# AdelinoX3.net
KiCad netlist of a schematic drawn in EAGLE
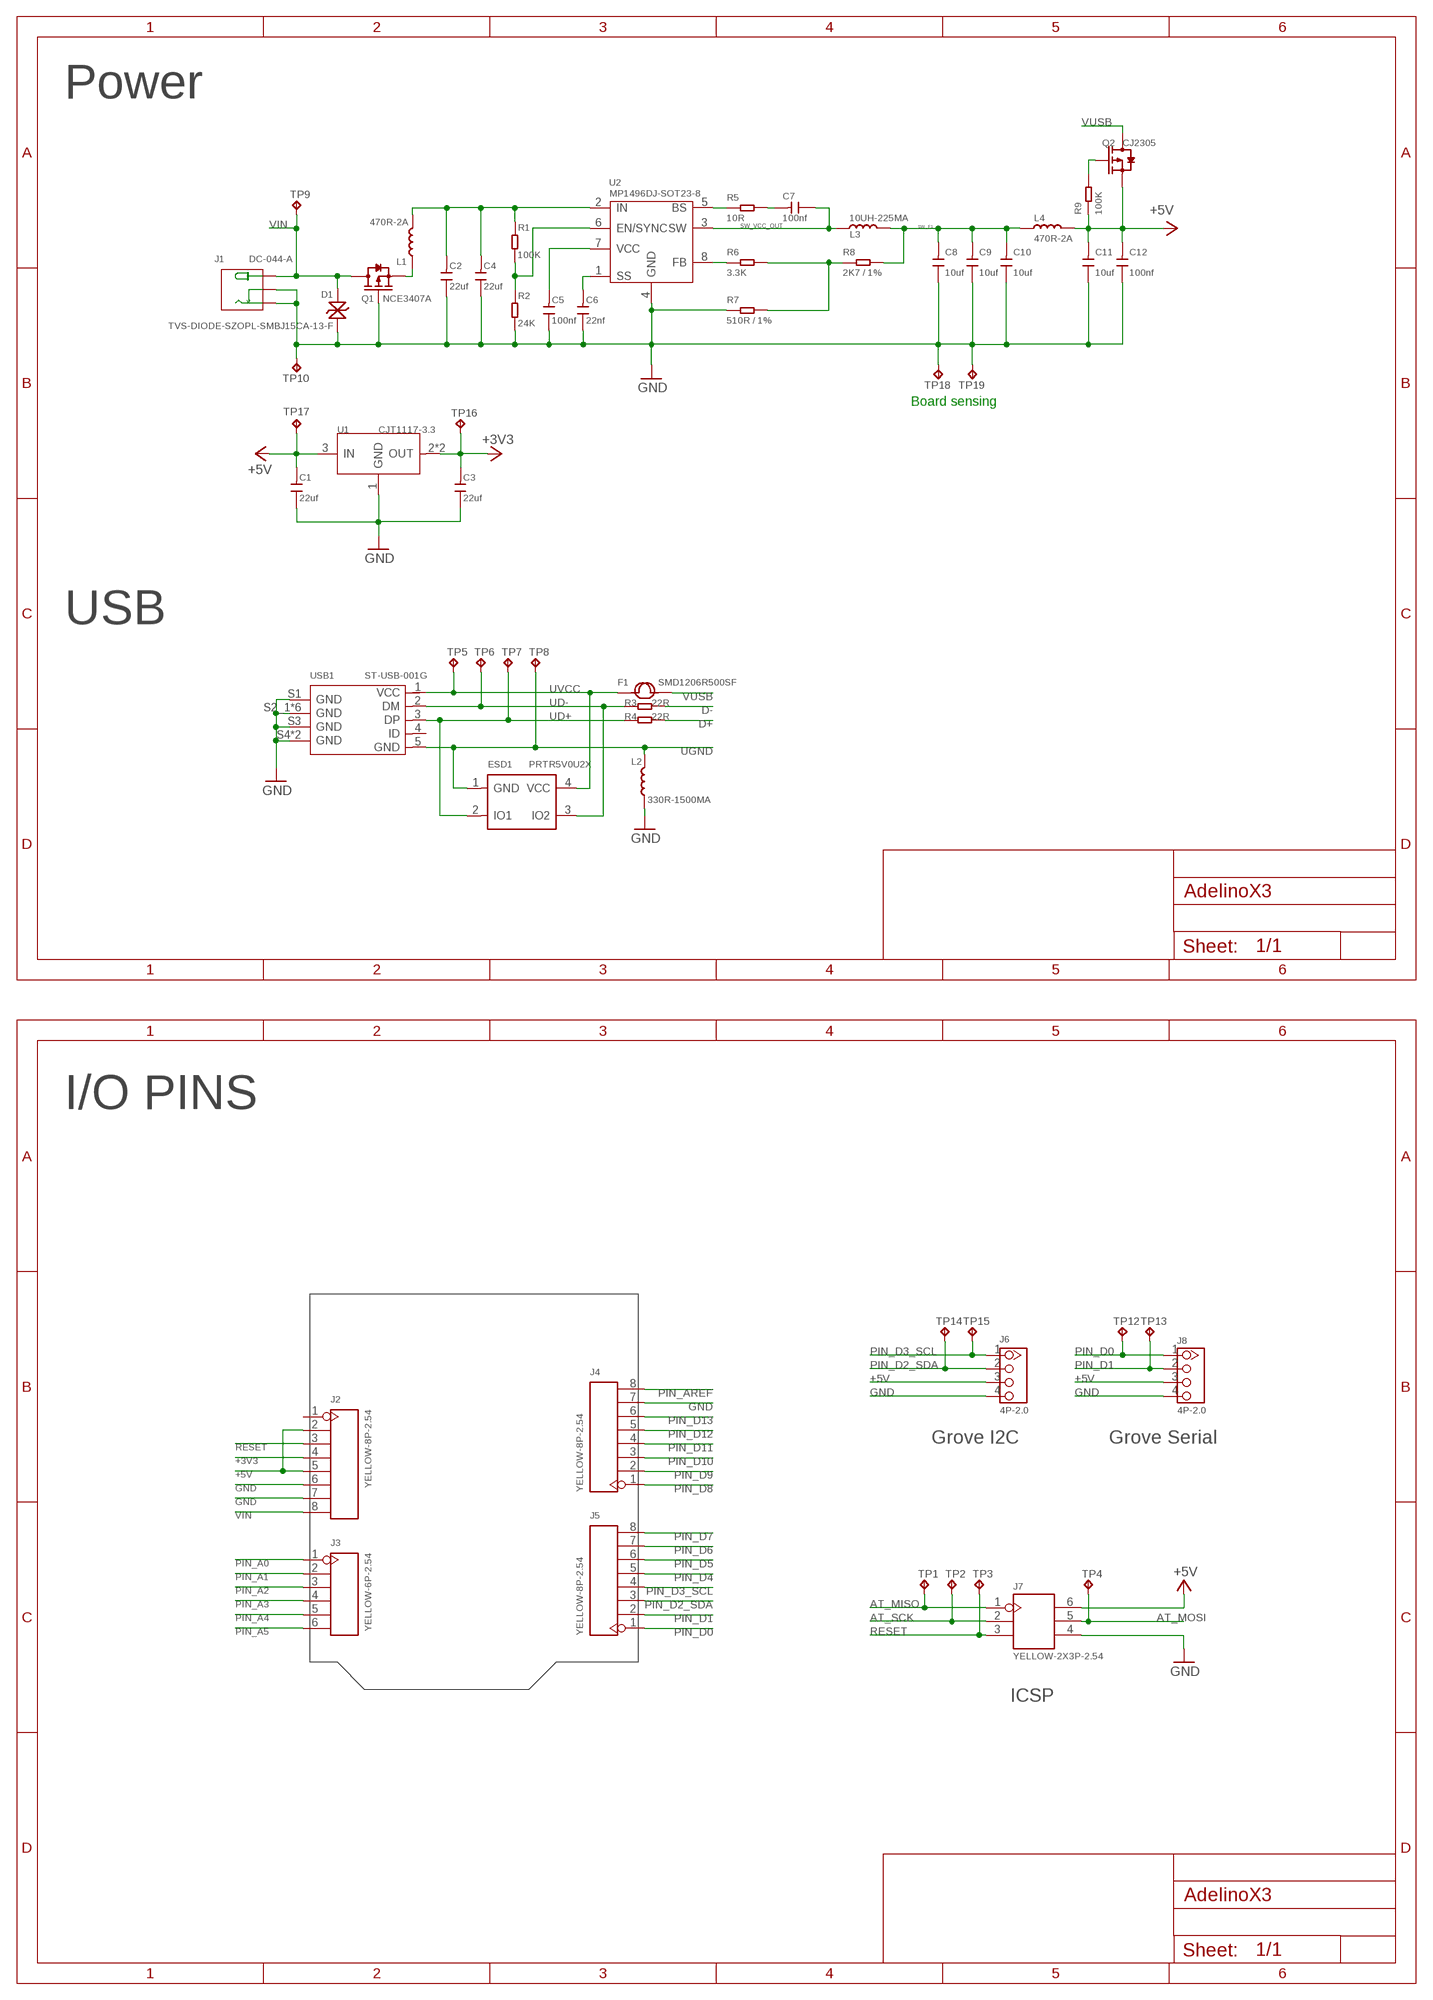
[diagram p0: schematic, sheet 1, part 1 of 2]
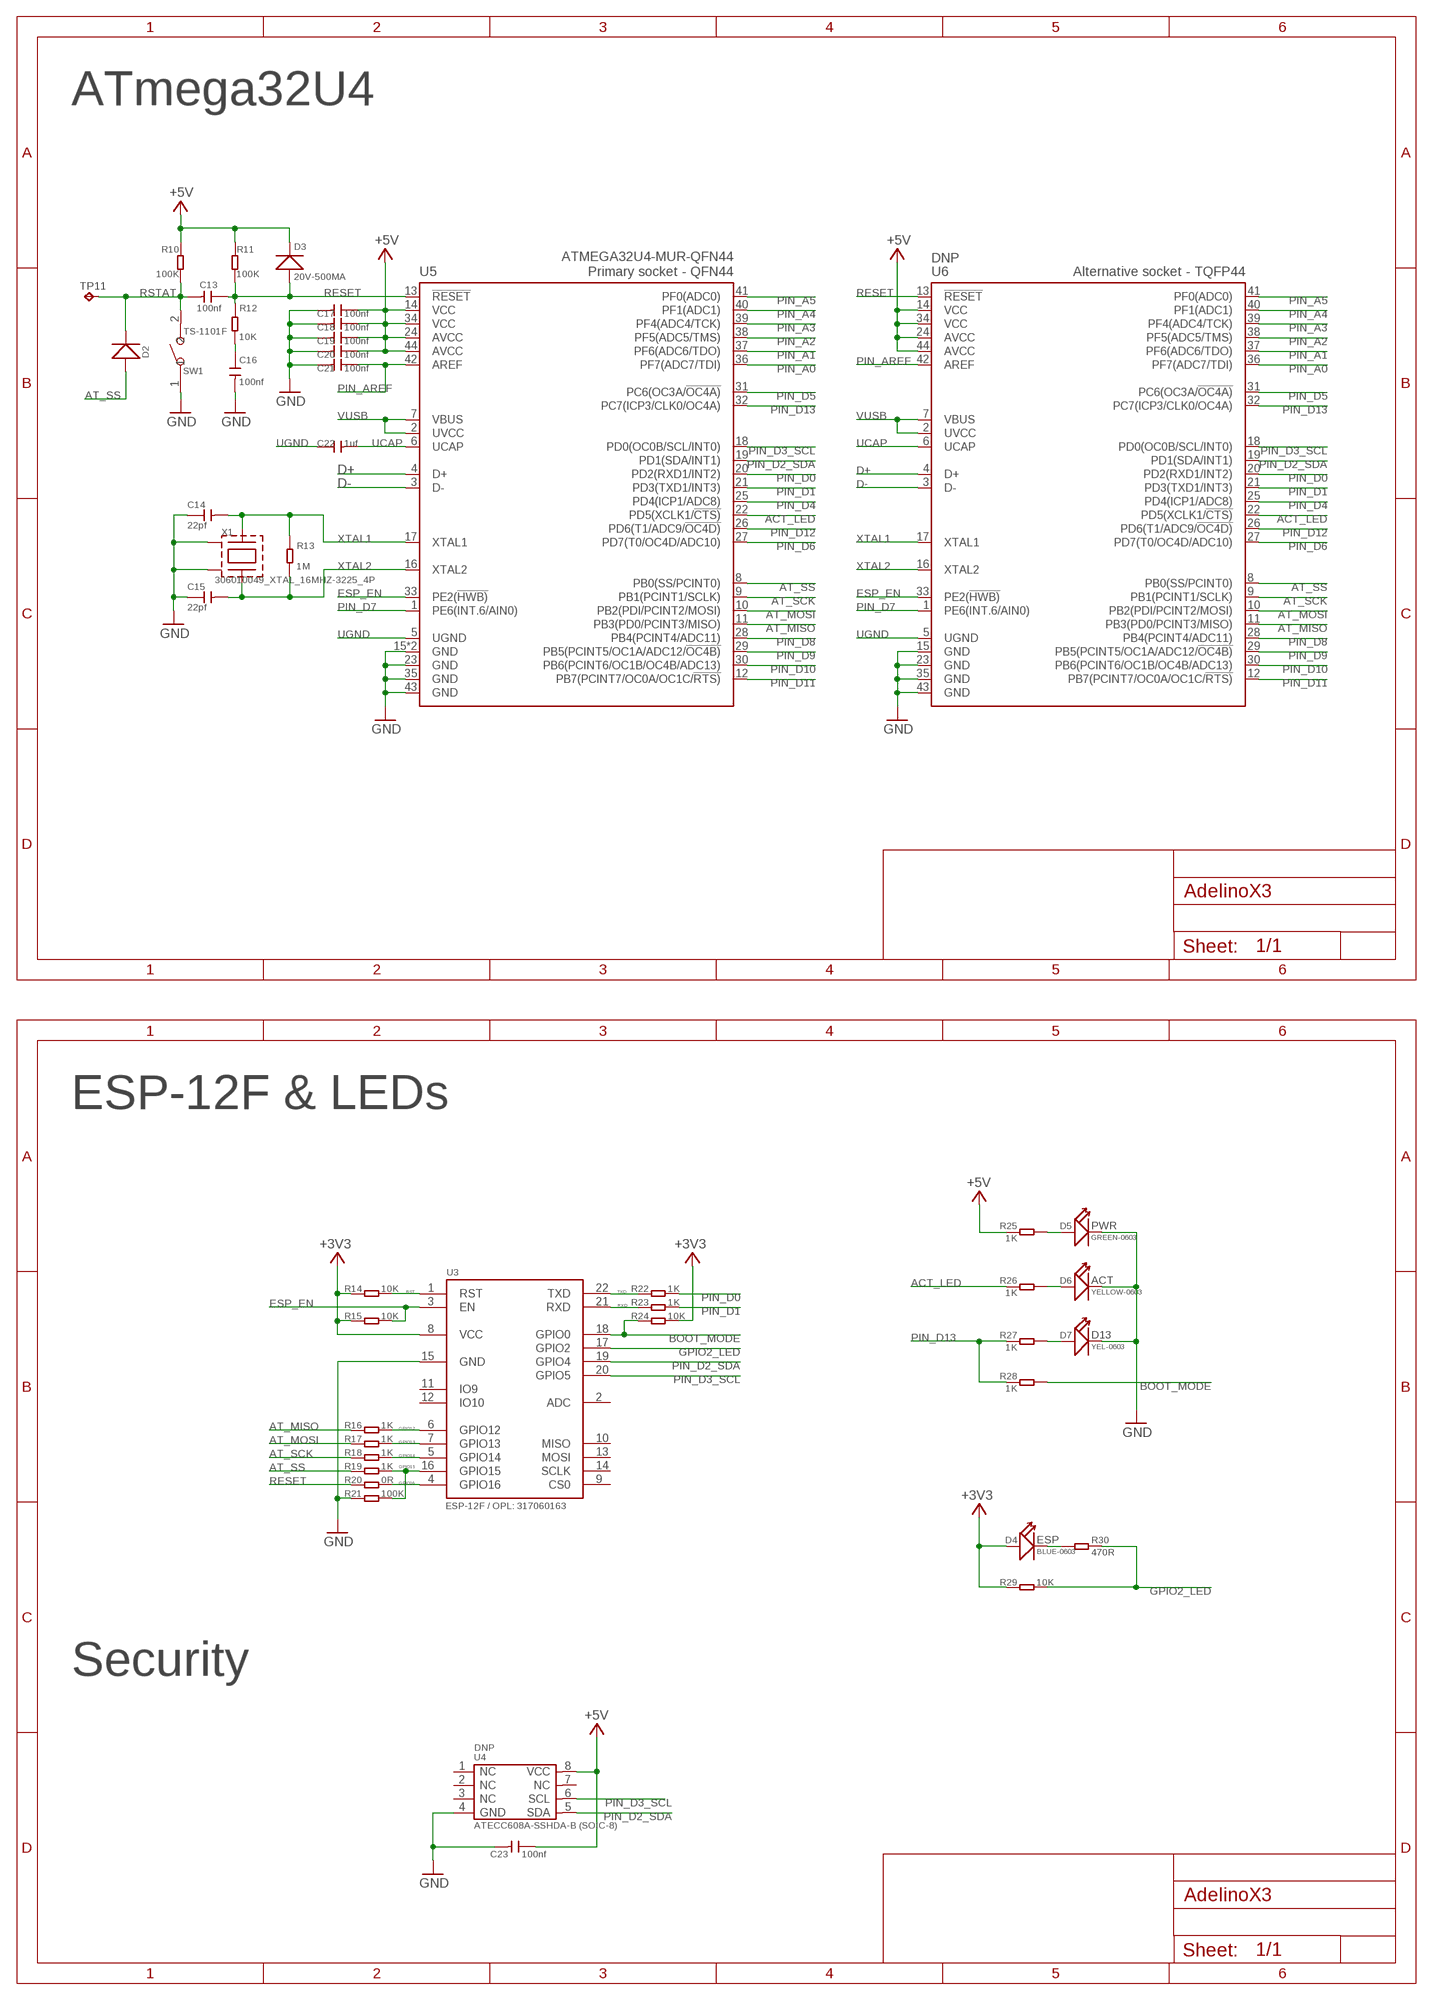
[diagram p1: schematic, sheet 1, part 2 of 2]

(export (version "E")
  (design (tool "Eeschema 10.0.6"))
  (components
    (comp (ref "C1")
      (value "22uf")
      (footprint "eagle-import:C1206")
      (libsource (lib "eagle-import") (part "Seeed-Capacitor_CERAMIC-22UF-16V-10%-X7R(1206)"))
    )
    (comp (ref "C2")
      (value "22uf")
      (footprint "eagle-import:C1206")
      (libsource (lib "eagle-import") (part "Seeed-Capacitor_CERAMIC-22UF-16V-10%-X7R(1206)"))
    )
    (comp (ref "C3")
      (value "22uf")
      (footprint "eagle-import:C1206")
      (libsource (lib "eagle-import") (part "CERAMIC-22UF-16V-10%-X7R(1206)"))
    )
    (comp (ref "C4")
      (value "22uf")
      (footprint "eagle-import:C1206")
      (libsource (lib "eagle-import") (part "Seeed-Capacitor_CERAMIC-22UF-16V-10%-X7R(1206)"))
    )
    (comp (ref "C5")
      (value "100nf")
      (footprint "eagle-import:C0603")
      (fields (field (name "MPN") "CC0603KRX7R9BB104"))
      (libsource (lib "eagle-import") (part "CERAMIC-100NF-50V-10%-X7R(0603)"))
    )
    (comp (ref "C6")
      (value "22nf")
      (footprint "eagle-import:C0603")
      (fields (field (name "MPN") "CC0603KRX7R9BB223"))
      (libsource (lib "eagle-import") (part "CERAMIC-22NF-50V-10%-X7R(0603)"))
    )
    (comp (ref "C7")
      (value "100nf")
      (footprint "eagle-import:C0603")
      (fields (field (name "MPN") "CC0603KRX7R9BB104"))
      (libsource (lib "eagle-import") (part "CERAMIC-100NF-50V-10%-X7R(0603)"))
    )
    (comp (ref "C8")
      (value "10uf")
      (footprint "eagle-import:C0805")
      (fields (field (name "MPN") "CC0805KKX5R8BB106"))
      (libsource (lib "eagle-import") (part "CERAMIC-10UF-25V-10%-X5R(0805)"))
    )
    (comp (ref "C9")
      (value "10uf")
      (footprint "eagle-import:C0805")
      (fields (field (name "MPN") "CC0805KKX5R8BB106"))
      (libsource (lib "eagle-import") (part "CERAMIC-10UF-25V-10%-X5R(0805)"))
    )
    (comp (ref "C10")
      (value "10uf")
      (footprint "eagle-import:C0805")
      (fields (field (name "MPN") "CC0805KKX5R8BB106"))
      (libsource (lib "eagle-import") (part "CERAMIC-10UF-25V-10%-X5R(0805)"))
    )
    (comp (ref "C11")
      (value "10uf")
      (footprint "eagle-import:C0805")
      (fields (field (name "MPN") "CC0805KKX5R8BB106"))
      (libsource (lib "eagle-import") (part "CERAMIC-10UF-25V-10%-X5R(0805)"))
    )
    (comp (ref "C12")
      (value "100nf")
      (footprint "eagle-import:C0603")
      (fields (field (name "MPN") "CC0603KRX7R9BB104"))
      (libsource (lib "eagle-import") (part "CERAMIC-100NF-50V-10%-X7R(0603)"))
    )
    (comp (ref "C13")
      (value "100nf")
      (footprint "eagle-import:C0603")
      (fields (field (name "MPN") "CC0603KRX7R9BB104"))
      (libsource (lib "eagle-import") (part "CERAMIC-100NF-50V-10%-X7R(0603)"))
    )
    (comp (ref "C14")
      (value "22pf")
      (footprint "eagle-import:C0603")
      (fields (field (name "MPN") "CC0603JRNPO9BN220"))
      (libsource (lib "eagle-import") (part "CERAMIC-22PF-50V-5%-NPO(0603)"))
    )
    (comp (ref "C15")
      (value "22pf")
      (footprint "eagle-import:C0603")
      (fields (field (name "MPN") "CC0603JRNPO9BN220"))
      (libsource (lib "eagle-import") (part "CERAMIC-22PF-50V-5%-NPO(0603)"))
    )
    (comp (ref "C16")
      (value "100nf")
      (footprint "eagle-import:C0603")
      (fields (field (name "MPN") "CC0603KRX7R9BB104"))
      (libsource (lib "eagle-import") (part "CERAMIC-100NF-50V-10%-X7R(0603)"))
    )
    (comp (ref "C17")
      (value "100nf")
      (footprint "eagle-import:C0603")
      (fields (field (name "MPN") "CC0603KRX7R9BB104"))
      (libsource (lib "eagle-import") (part "CERAMIC-100NF-50V-10%-X7R(0603)"))
    )
    (comp (ref "C18")
      (value "100nf")
      (footprint "eagle-import:C0603")
      (fields (field (name "MPN") "CC0603KRX7R9BB104"))
      (libsource (lib "eagle-import") (part "CERAMIC-100NF-50V-10%-X7R(0603)"))
    )
    (comp (ref "C19")
      (value "100nf")
      (footprint "eagle-import:C0603")
      (fields (field (name "MPN") "CC0603KRX7R9BB104"))
      (libsource (lib "eagle-import") (part "CERAMIC-100NF-50V-10%-X7R(0603)"))
    )
    (comp (ref "C20")
      (value "100nf")
      (footprint "eagle-import:C0603")
      (fields (field (name "MPN") "CC0603KRX7R9BB104"))
      (libsource (lib "eagle-import") (part "CERAMIC-100NF-50V-10%-X7R(0603)"))
    )
    (comp (ref "C21")
      (value "100nf")
      (footprint "eagle-import:C0603")
      (fields (field (name "MPN") "CC0603KRX7R9BB104"))
      (libsource (lib "eagle-import") (part "CERAMIC-100NF-50V-10%-X7R(0603)"))
    )
    (comp (ref "C22")
      (value "1uf")
      (footprint "eagle-import:C0603")
      (fields (field (name "MPN") "CC0603KRX7R8BB105"))
      (libsource (lib "eagle-import") (part "CERAMIC-1UF-25V-10%-X7R(0603)"))
    )
    (comp (ref "C23")
      (value "100nf")
      (footprint "eagle-import:C0603")
      (fields (field (name "MPN") "CC0603KRX7R9BB104"))
      (libsource (lib "eagle-import") (part "Seeed-Capacitor_CERAMIC-100NF-50V-10%-X7R(0603)"))
    )
    (comp (ref "D1")
      (value "TVS-DIODE-SZOPL-SMBJ15CA-13-F")
      (footprint "eagle-import:DO-214AA")
      (fields (field (name "MPN") "SMBJ15CA-13-F"))
      (libsource (lib "eagle-import") (part "TVS-DIODE-SZOPL-SMBJ15CA-13-F"))
    )
    (comp (ref "D2")
      (value "20V-500MA")
      (footprint "eagle-import:SOD-123")
      (fields (field (name "MPN") "MBR0520LT1G"))
      (libsource (lib "eagle-import") (part "SMD-DIODE-SCHOTTKY-20V-500MA(SOD-123)P"))
    )
    (comp (ref "D3")
      (value "20V-500MA")
      (footprint "eagle-import:SOD-123")
      (fields (field (name "MPN") "MBR0520LT1G"))
      (libsource (lib "eagle-import") (part "SMD-DIODE-SCHOTTKY-20V-500MA(SOD-123)P"))
    )
    (comp (ref "D4")
      (value "BLUE-0603")
      (footprint "eagle-import:LED-0603")
      (fields (field (name "MPN") "19-217-BHC-ZL1M2RY-3T") (field (name "LABEL") "ESP"))
      (libsource (lib "eagle-import") (part "SMD-LED-CLEAR-BLUE(0603)"))
    )
    (comp (ref "D5")
      (value "GREEN-0603")
      (footprint "eagle-import:LED-0603")
      (fields (field (name "MPN") "19-217-G7C-AN1P2-3T") (field (name "LABEL") "PWR"))
      (libsource (lib "eagle-import") (part "SMD-LED-CLEAR-GREEN(0603)"))
    )
    (comp (ref "D6")
      (value "YELLOW-0603")
      (footprint "eagle-import:LED-0603")
      (fields (field (name "MPN") "19-217-Y5C-AM1N1VY-3T") (field (name "LABEL") "ACT"))
      (libsource (lib "eagle-import") (part "SMD-LED-CLEAR-YELLOW(0603)"))
    )
    (comp (ref "D7")
      (value "YEL-0603")
      (footprint "eagle-import:LED-0603")
      (fields (field (name "MPN") "19-217-Y5C-AM1N1VY-3T") (field (name "LABEL") "D13"))
      (libsource (lib "eagle-import") (part "SMD-LED-CLEAR-YELLOW(0603)"))
    )
    (comp (ref "ESD1")
      (value "PRTR5V0U2X")
      (footprint "eagle-import:SOT-143B")
      (fields (field (name "MPN") "NXP;PRTR5V0U2X,215"))
      (libsource (lib "eagle-import") (part "SMD-DIODE-TVS-5.5V"))
    )
    (comp (ref "F1")
      (value "SMD1206R500SF")
      (footprint "eagle-import:F1206")
      (libsource (lib "eagle-import") (part "SMD-PPTC-500MA(1206)"))
    )
    (comp (ref "J1")
      (value "DC-044-A")
      (footprint "eagle-import:DCJ3P-11.6X9.6X7.0MM")
      (fields (field (name "MPN") "JACK-DC-044-A"))
      (libsource (lib "eagle-import") (part "JACK-DC-044-A"))
    )
    (comp (ref "J2")
      (value "YELLOW-8P-2.54")
      (footprint "eagle-import:H8-2.54")
      (fields (field (name "MPN") "F185-1108A1BSYC1"))
      (libsource (lib "eagle-import") (part "DIP-YELLOW-FEMALE-HEADER(8P-2.54)"))
    )
    (comp (ref "J3")
      (value "YELLOW-6P-2.54")
      (footprint "eagle-import:H6-2.54")
      (fields (field (name "MPN") "F185-1106A1BSYA3"))
      (libsource (lib "eagle-import") (part "DIP-YELLOW-FEMALE-HEADER-VERT(6P-2.54)"))
    )
    (comp (ref "J4")
      (value "YELLOW-8P-2.54")
      (footprint "eagle-import:H8-2.54")
      (fields (field (name "MPN") "F185-1108A1BSYC1"))
      (libsource (lib "eagle-import") (part "DIP-YELLOW-FEMALE-HEADER(8P-2.54)"))
    )
    (comp (ref "J5")
      (value "YELLOW-8P-2.54")
      (footprint "eagle-import:H8-2.54")
      (fields (field (name "MPN") "F185-1108A1BSYC1"))
      (libsource (lib "eagle-import") (part "DIP-YELLOW-FEMALE-HEADER(8P-2.54)"))
    )
    (comp (ref "J6")
      (value "4P-2.0")
      (footprint "eagle-import:HW4-2.0")
      (libsource (lib "eagle-import") (part "GROVE-CONNECTOR-DIP(4P-2.0)"))
    )
    (comp (ref "J7")
      (value "YELLOW-2X3P-2.54")
      (footprint "eagle-import:H2X3-2.54")
      (fields (field (name "MPN") "P125-1203A0BS116A2"))
      (libsource (lib "eagle-import") (part "DIP-YELLOW-MALE-HEADER-VERT(2X3P-2.54)"))
    )
    (comp (ref "J8")
      (value "4P-2.0")
      (footprint "eagle-import:HW4-2.0")
      (libsource (lib "eagle-import") (part "GROVE-CONNECTOR-DIP(4P-2.0)"))
    )
    (comp (ref "L1")
      (value "470R-2A")
      (footprint "eagle-import:L0805")
      (fields (field (name "MPN") "WLB2012-471T20"))
      (libsource (lib "eagle-import") (part "SMD-FERRITE-BEAD-470R-2A(0805)'0805'"))
    )
    (comp (ref "L2")
      (value "330R-1500MA")
      (footprint "eagle-import:L0805")
      (fields (field (name "MPN") "BLM21PG331SN1D"))
      (libsource (lib "eagle-import") (part "SMD-FERRITE-BEAD-330R-1500MA(0805)'0805'"))
    )
    (comp (ref "L3")
      (value "10UH-225MA")
      (footprint "eagle-import:L5040S")
      (libsource (lib "eagle-import") (part "SMD-INDUCTOR-10UH-20%-2.35A(2P-5X5X4MM)"))
    )
    (comp (ref "L4")
      (value "470R-2A")
      (footprint "eagle-import:L0805")
      (fields (field (name "MPN") "WLB2012-471T20"))
      (libsource (lib "eagle-import") (part "SMD-FERRITE-BEAD-470R-2A(0805)'0805'"))
    )
    (comp (ref "Q1")
      (value "NCE3407A")
      (footprint "eagle-import:SOT-23")
      (libsource (lib "eagle-import") (part "SMD-MOSFET-P-CH-VDC=30V-ID=4.3A-NCE3407A(SOT-23)"))
    )
    (comp (ref "Q2")
      (value "CJ2305")
      (footprint "eagle-import:SOT-23")
      (libsource (lib "eagle-import") (part "SMD-MOSFET-P-CH-8V-4.1A-CJ2305(SOT-23)"))
    )
    (comp (ref "R1")
      (value "100K")
      (footprint "eagle-import:R0603")
      (fields (field (name "MPN") "RC0603JR-07100KL"))
      (libsource (lib "eagle-import") (part "SMD-RES-100K-5%-1/10W(0603)"))
    )
    (comp (ref "R2")
      (value "24K")
      (footprint "eagle-import:R0603")
      (libsource (lib "eagle-import") (part "SMD-RES-24K-1%-1/10W(0603)"))
    )
    (comp (ref "R3")
      (value "22R")
      (footprint "eagle-import:R0603")
      (fields (field (name "MPN") "RC0603JR-0722RL"))
      (libsource (lib "eagle-import") (part "SMD-RES-22R-5%-1/10W(0603)"))
    )
    (comp (ref "R4")
      (value "22R")
      (footprint "eagle-import:R0603")
      (fields (field (name "MPN") "RC0603JR-0722RL"))
      (libsource (lib "eagle-import") (part "SMD-RES-22R-5%-1/10W(0603)"))
    )
    (comp (ref "R5")
      (value "10R")
      (footprint "eagle-import:R0603")
      (fields (field (name "MPN") "RC0603FR-0710RL"))
      (libsource (lib "eagle-import") (part "SMD-RES-10R-1%-1/10W(0603)"))
    )
    (comp (ref "R6")
      (value "3.3K")
      (footprint "eagle-import:R0603")
      (libsource (lib "eagle-import") (part "SMD-RES-3.3K-5%-1/10W(0603)"))
    )
    (comp (ref "R7")
      (value "3K / 1%")
      (footprint "eagle-import:R0603")
      (fields (field (name "R") "510R / 1%"))
      (libsource (lib "eagle-import") (part "SMD-RES-510R-1%-1/10W(0603)"))
    )
    (comp (ref "R8")
      (value "2K7 / 1%")
      (footprint "eagle-import:R0603")
      (fields (field (name "R") "2K7 / 1%"))
      (libsource (lib "eagle-import") (part "SMD-RES-2.7K-1%-1/10W(0603)"))
    )
    (comp (ref "R9")
      (value "100K")
      (footprint "eagle-import:R0603")
      (fields (field (name "MPN") "RC0603JR-07100KL"))
      (libsource (lib "eagle-import") (part "SMD-RES-100K-5%-1/10W(0603)"))
    )
    (comp (ref "R10")
      (value "100K")
      (footprint "eagle-import:R0603")
      (fields (field (name "MPN") "RC0603JR-07100KL"))
      (libsource (lib "eagle-import") (part "SMD-RES-100K-5%-1/10W(0603)"))
    )
    (comp (ref "R11")
      (value "100K")
      (footprint "eagle-import:R0603")
      (fields (field (name "MPN") "RC0603JR-07100KL"))
      (libsource (lib "eagle-import") (part "SMD-RES-100K-5%-1/10W(0603)"))
    )
    (comp (ref "R12")
      (value "10K")
      (footprint "eagle-import:R0603")
      (fields (field (name "MPN") "RC0603JR-0710KL"))
      (libsource (lib "eagle-import") (part "SMD-RES-10K-5%-1/10W(0603)"))
    )
    (comp (ref "R13")
      (value "1M")
      (footprint "eagle-import:R0603")
      (fields (field (name "MPN") "RC0603JR-071ML"))
      (libsource (lib "eagle-import") (part "SMD-RES-1M-5%-1/10W(0603)"))
    )
    (comp (ref "R14")
      (value "10K")
      (footprint "eagle-import:R0603")
      (fields (field (name "MPN") "RC0603JR-0710KL"))
      (libsource (lib "eagle-import") (part "SMD-RES-10K-5%-1/10W(0603)"))
    )
    (comp (ref "R15")
      (value "10K")
      (footprint "eagle-import:R0603")
      (fields (field (name "MPN") "RC0603JR-0710KL"))
      (libsource (lib "eagle-import") (part "SMD-RES-10K-5%-1/10W(0603)"))
    )
    (comp (ref "R16")
      (value "1K")
      (footprint "eagle-import:R0603")
      (fields (field (name "MPN") "RC0603JR-071KL"))
      (libsource (lib "eagle-import") (part "SMD-RES-1K-5%-1/10W(0603)"))
    )
    (comp (ref "R17")
      (value "1K")
      (footprint "eagle-import:R0603")
      (fields (field (name "MPN") "RC0603JR-071KL"))
      (libsource (lib "eagle-import") (part "SMD-RES-1K-5%-1/10W(0603)"))
    )
    (comp (ref "R18")
      (value "1K")
      (footprint "eagle-import:R0603")
      (fields (field (name "MPN") "RC0603JR-071KL"))
      (libsource (lib "eagle-import") (part "SMD-RES-1K-5%-1/10W(0603)"))
    )
    (comp (ref "R19")
      (value "1K")
      (footprint "eagle-import:R0603")
      (fields (field (name "MPN") "RC0603JR-071KL"))
      (libsource (lib "eagle-import") (part "SMD-RES-1K-5%-1/10W(0603)"))
    )
    (comp (ref "R20")
      (value "0R")
      (footprint "eagle-import:R0603")
      (fields (field (name "MPN") "RC0603JR-070RL"))
      (libsource (lib "eagle-import") (part "SMD-RES-0R-5%-1/10W(0603)"))
    )
    (comp (ref "R21")
      (value "100K")
      (footprint "eagle-import:R0603")
      (fields (field (name "MPN") "RC0603JR-07100KL"))
      (libsource (lib "eagle-import") (part "SMD-RES-100K-5%-1/10W(0603)"))
    )
    (comp (ref "R22")
      (value "1K")
      (footprint "eagle-import:R0603")
      (fields (field (name "MPN") "RC0603JR-071KL"))
      (libsource (lib "eagle-import") (part "SMD-RES-1K-5%-1/10W(0603)"))
    )
    (comp (ref "R23")
      (value "1K")
      (footprint "eagle-import:R0603")
      (fields (field (name "MPN") "RC0603JR-071KL"))
      (libsource (lib "eagle-import") (part "SMD-RES-1K-5%-1/10W(0603)"))
    )
    (comp (ref "R24")
      (value "10K")
      (footprint "eagle-import:R0603")
      (fields (field (name "MPN") "RC0603JR-0710KL"))
      (libsource (lib "eagle-import") (part "SMD-RES-10K-5%-1/10W(0603)"))
    )
    (comp (ref "R25")
      (value "1K")
      (footprint "eagle-import:R0603")
      (fields (field (name "MPN") "RC0603JR-071KL"))
      (libsource (lib "eagle-import") (part "SMD-RES-1K-5%-1/10W(0603)"))
    )
    (comp (ref "R26")
      (value "1K")
      (footprint "eagle-import:R0603")
      (fields (field (name "MPN") "RC0603JR-071KL"))
      (libsource (lib "eagle-import") (part "SMD-RES-1K-5%-1/10W(0603)"))
    )
    (comp (ref "R27")
      (value "1K")
      (footprint "eagle-import:R0603")
      (fields (field (name "MPN") "RC0603JR-071KL"))
      (libsource (lib "eagle-import") (part "SMD-RES-1K-5%-1/10W(0603)"))
    )
    (comp (ref "R28")
      (value "1K")
      (footprint "eagle-import:R0603")
      (fields (field (name "MPN") "RC0603JR-071KL"))
      (libsource (lib "eagle-import") (part "SMD-RES-1K-5%-1/10W(0603)"))
    )
    (comp (ref "R29")
      (value "10K")
      (footprint "eagle-import:R0603")
      (fields (field (name "MPN") "RC0603JR-0710KL"))
      (libsource (lib "eagle-import") (part "SMD-RES-10K-5%-1/10W(0603)"))
    )
    (comp (ref "R30")
      (value "470R")
      (footprint "eagle-import:R0603")
      (fields (field (name "MPN") "RC0603JR-07470RL"))
      (libsource (lib "eagle-import") (part "SMD-RES-470R-5%-1/10W(0603)"))
    )
    (comp (ref "SW1")
      (value "TS-1101F")
      (footprint "eagle-import:SW2-5.0-6.0X3.0X4.3MM")
      (libsource (lib "eagle-import") (part "DIP-BUTTON(2P-6.0X3.0X4.3MM)-TS-1101F"))
    )
    (comp (ref "TP1")
      (value "TPTP16R")
      (footprint "eagle-import:TP16R")
      (libsource (lib "eagle-import") (part "TPTP16R"))
    )
    (comp (ref "TP2")
      (value "TPTP16R")
      (footprint "eagle-import:TP16R")
      (libsource (lib "eagle-import") (part "TPTP16R"))
    )
    (comp (ref "TP3")
      (value "TPTP16R")
      (footprint "eagle-import:TP16R")
      (libsource (lib "eagle-import") (part "TPTP16R"))
    )
    (comp (ref "TP4")
      (value "TPTP16R")
      (footprint "eagle-import:TP16R")
      (libsource (lib "eagle-import") (part "TPTP16R"))
    )
    (comp (ref "TP5")
      (value "TPTP16R")
      (footprint "eagle-import:TP16R")
      (libsource (lib "eagle-import") (part "TPTP16R"))
    )
    (comp (ref "TP6")
      (value "TPTP16R")
      (footprint "eagle-import:TP16R")
      (libsource (lib "eagle-import") (part "TPTP16R"))
    )
    (comp (ref "TP7")
      (value "TPTP16R")
      (footprint "eagle-import:TP16R")
      (libsource (lib "eagle-import") (part "TPTP16R"))
    )
    (comp (ref "TP8")
      (value "TPTP16R")
      (footprint "eagle-import:TP16R")
      (libsource (lib "eagle-import") (part "TPTP16R"))
    )
    (comp (ref "TP9")
      (value "TPTP16R")
      (footprint "eagle-import:TP16R")
      (libsource (lib "eagle-import") (part "TPTP16R"))
    )
    (comp (ref "TP10")
      (value "TPTP16R")
      (footprint "eagle-import:TP16R")
      (libsource (lib "eagle-import") (part "TPTP16R"))
    )
    (comp (ref "TP11")
      (value "TPTP16R")
      (footprint "eagle-import:TP16R")
      (libsource (lib "eagle-import") (part "TPTP16R"))
    )
    (comp (ref "TP12")
      (value "TPTP16R")
      (footprint "eagle-import:TP16R")
      (libsource (lib "eagle-import") (part "TPTP16R"))
    )
    (comp (ref "TP13")
      (value "TPTP16R")
      (footprint "eagle-import:TP16R")
      (libsource (lib "eagle-import") (part "TPTP16R"))
    )
    (comp (ref "TP14")
      (value "TPTP16R")
      (footprint "eagle-import:TP16R")
      (libsource (lib "eagle-import") (part "TPTP16R"))
    )
    (comp (ref "TP15")
      (value "TPTP16R")
      (footprint "eagle-import:TP16R")
      (libsource (lib "eagle-import") (part "TPTP16R"))
    )
    (comp (ref "TP16")
      (value "TPTP16R")
      (footprint "eagle-import:TP16R")
      (libsource (lib "eagle-import") (part "TPTP16R"))
    )
    (comp (ref "TP17")
      (value "TPTP16R")
      (footprint "eagle-import:TP16R")
      (libsource (lib "eagle-import") (part "TPTP16R"))
    )
    (comp (ref "TP18")
      (value "TPTP16R")
      (footprint "eagle-import:TP16R")
      (libsource (lib "eagle-import") (part "TPTP16R"))
    )
    (comp (ref "TP19")
      (value "TPTP16R")
      (footprint "eagle-import:TP16R")
      (libsource (lib "eagle-import") (part "TPTP16R"))
    )
    (comp (ref "U1")
      (value "CJT1117-3.3")
      (footprint "eagle-import:SOT-223")
      (libsource (lib "eagle-import") (part "PMIC-CJT1117-3.3(SOT223)"))
    )
    (comp (ref "U2")
      (value "MP1496DJ-SOT23-8")
      (footprint "eagle-import:SOT-23-8")
      (fields (field (name "MPN") "MP1496DJ"))
      (libsource (lib "eagle-import") (part "PMIC-MP1496DJ(SOT23-8)"))
    )
    (comp (ref "U3")
      (value "ESP-12F / OPL: 317060163")
      (footprint "eagle-import:ESP-12F")
      (libsource (lib "eagle-import") (part "ESP-12F"))
    )
    (comp (ref "U4")
      (value "DNP")
      (footprint "eagle-import:SOIC8-1.27-5X4MM")
      (fields
        (field (name "MPN") "ATECC608")
        (field (name "DESC") "ATECC608A-SSHDA-B (SOIC-8)")
        (field (name "MPN_1") "ATECC608A-SSHDA-B")
      )
      (libsource (lib "eagle-import") (part "ATECC608(SOIC8)"))
    )
    (comp (ref "U5")
      (value "ATMEGA32U4-MUR-QFN44")
      (footprint "eagle-import:QFN44G-0.5-7X7MM")
      (fields (field (name "MPN") "ATMEGA32U4-MUR") (field (name "DESC") "Primary socket - QFN44"))
      (libsource (lib "eagle-import") (part "MCU-ATMEGA32U4-MUR(VQFN44)"))
    )
    (comp (ref "U6")
      (value "DNP")
      (footprint "eagle-import:TQFP44-0.8-9.6X9.6MM")
      (fields (field (name "MPN") "ATMEGA32U4") (field (name "DESC") "Alternative socket - TQFP44"))
      (libsource (lib "eagle-import") (part "MCU-ATMEGA32U4-AU(TQFP44)"))
    )
    (comp (ref "USB1")
      (value "ST-USB-001G")
      (footprint "eagle-import:MICRO-USB5+4P-SMD-0.65-B")
      (libsource (lib "eagle-import") (part "MICRO-USB-SMD-B-WITHOUT-POST-W/P(ST-USB-001G)"))
    )
    (comp (ref "X1")
      (value "306010049_XTAL_16MHZ-3225_4P")
      (footprint "eagle-import:X3225_4P")
      (libsource (lib "eagle-import") (part "306010049_XTAL_16MHZ-3225_4P"))
    )
  )
  (nets
    (net (code "1") (name "+3V3") (class "Default")
      (node (ref "C3") (pin "2") (pinfunction "2_2") (pintype "passive"))
      (node (ref "D4") (pin "+") (pinfunction "+_+") (pintype "passive"))
      (node (ref "J2") (pin "4") (pinfunction "4_4") (pintype "bidirectional"))
      (node (ref "R14") (pin "1") (pinfunction "1_1") (pintype "passive"))
      (node (ref "R15") (pin "1") (pinfunction "1_1") (pintype "passive"))
      (node (ref "R24") (pin "2") (pinfunction "2_2") (pintype "passive"))
      (node (ref "R29") (pin "1") (pinfunction "1_1") (pintype "passive"))
      (node (ref "TP16") (pin "TP") (pinfunction "TP_TP") (pintype "input"))
      (node (ref "U1") (pin "2") (pinfunction "OUT_2") (pintype "bidirectional"))
      (node (ref "U1") (pin "TER") (pinfunction "OUT_TER") (pintype "bidirectional"))
      (node (ref "U3") (pin "8") (pinfunction "VCC_8") (pintype "bidirectional"))
    )
    (net (code "2") (name "+5V") (class "Default")
      (node (ref "C1") (pin "2") (pinfunction "2_2") (pintype "passive"))
      (node (ref "C11") (pin "2") (pinfunction "2_2") (pintype "passive"))
      (node (ref "C12") (pin "2") (pinfunction "2_2") (pintype "passive"))
      (node (ref "C17") (pin "1") (pinfunction "1_1") (pintype "passive"))
      (node (ref "C18") (pin "1") (pinfunction "1_1") (pintype "passive"))
      (node (ref "C19") (pin "1") (pinfunction "1_1") (pintype "passive"))
      (node (ref "C20") (pin "1") (pinfunction "1_1") (pintype "passive"))
      (node (ref "C23") (pin "1") (pinfunction "1_1") (pintype "passive"))
      (node (ref "D3") (pin "-") (pinfunction "-_-") (pintype "passive"))
      (node (ref "J2") (pin "2") (pinfunction "2_2") (pintype "bidirectional"))
      (node (ref "J2") (pin "5") (pinfunction "5_5") (pintype "bidirectional"))
      (node (ref "J6") (pin "3") (pinfunction "3_3") (pintype "bidirectional"))
      (node (ref "J7") (pin "6") (pinfunction "6_6") (pintype "bidirectional"))
      (node (ref "J8") (pin "3") (pinfunction "3_3") (pintype "bidirectional"))
      (node (ref "L4") (pin "2") (pinfunction "2_2") (pintype "passive"))
      (node (ref "Q2") (pin "2") (pinfunction "S_2") (pintype "passive"))
      (node (ref "R10") (pin "1") (pinfunction "1_1") (pintype "passive"))
      (node (ref "R11") (pin "2") (pinfunction "2_2") (pintype "passive"))
      (node (ref "R25") (pin "1") (pinfunction "1_1") (pintype "passive"))
      (node (ref "R9") (pin "1") (pinfunction "1_1") (pintype "passive"))
      (node (ref "TP17") (pin "TP") (pinfunction "TP_TP") (pintype "input"))
      (node (ref "U1") (pin "3") (pinfunction "IN_3") (pintype "bidirectional"))
      (node (ref "U4") (pin "8") (pinfunction "VCC_8") (pintype "power_in"))
      (node (ref "U5") (pin "14") (pinfunction "VCC_14") (pintype "bidirectional"))
      (node (ref "U5") (pin "24") (pinfunction "AVCC_24") (pintype "bidirectional"))
      (node (ref "U5") (pin "34") (pinfunction "VCC_34") (pintype "bidirectional"))
      (node (ref "U5") (pin "44") (pinfunction "AVCC_44") (pintype "bidirectional"))
      (node (ref "U6") (pin "14") (pinfunction "VCC_14") (pintype "bidirectional"))
      (node (ref "U6") (pin "24") (pinfunction "AVCC_24") (pintype "bidirectional"))
      (node (ref "U6") (pin "34") (pinfunction "VCC_34") (pintype "bidirectional"))
      (node (ref "U6") (pin "44") (pinfunction "AVCC_44") (pintype "bidirectional"))
    )
    (net (code "3") (name "/ACT_LED") (class "Default")
      (node (ref "R26") (pin "1") (pinfunction "1_1") (pintype "passive"))
      (node (ref "U5") (pin "22") (pinfunction "PD5(XCLK1/~{CTS})_22") (pintype "bidirectional"))
      (node (ref "U6") (pin "22") (pinfunction "PD5(XCLK1/~{CTS})_22") (pintype "bidirectional"))
    )
    (net (code "4") (name "/AT_MISO") (class "Default")
      (node (ref "J7") (pin "1") (pinfunction "1_1") (pintype "bidirectional"))
      (node (ref "R16") (pin "1") (pinfunction "1_1") (pintype "passive"))
      (node (ref "TP1") (pin "TP") (pinfunction "TP_TP") (pintype "input"))
      (node (ref "U5") (pin "11") (pinfunction "PB3(PD0/PCINT3/MISO)_11") (pintype "bidirectional"))
      (node (ref "U6") (pin "11") (pinfunction "PB3(PD0/PCINT3/MISO)_11") (pintype "bidirectional"))
    )
    (net (code "5") (name "/AT_MOSI") (class "Default")
      (node (ref "J7") (pin "5") (pinfunction "5_5") (pintype "bidirectional"))
      (node (ref "R17") (pin "1") (pinfunction "1_1") (pintype "passive"))
      (node (ref "TP4") (pin "TP") (pinfunction "TP_TP") (pintype "input"))
      (node (ref "U5") (pin "10") (pinfunction "PB2(PDI/PCINT2/MOSI)_10") (pintype "bidirectional"))
      (node (ref "U6") (pin "10") (pinfunction "PB2(PDI/PCINT2/MOSI)_10") (pintype "bidirectional"))
    )
    (net (code "6") (name "/AT_SCK") (class "Default")
      (node (ref "J7") (pin "2") (pinfunction "2_2") (pintype "bidirectional"))
      (node (ref "R18") (pin "1") (pinfunction "1_1") (pintype "passive"))
      (node (ref "TP2") (pin "TP") (pinfunction "TP_TP") (pintype "input"))
      (node (ref "U5") (pin "9") (pinfunction "PB1(PCINT1/SCLK)_9") (pintype "bidirectional"))
      (node (ref "U6") (pin "9") (pinfunction "PB1(PCINT1/SCLK)_9") (pintype "bidirectional"))
    )
    (net (code "7") (name "/AT_SS") (class "Default")
      (node (ref "D2") (pin "+") (pinfunction "+_+") (pintype "passive"))
      (node (ref "R19") (pin "1") (pinfunction "1_1") (pintype "passive"))
      (node (ref "U5") (pin "8") (pinfunction "PB0(SS/PCINT0)_8") (pintype "bidirectional"))
      (node (ref "U6") (pin "8") (pinfunction "PB0(SS/PCINT0)_8") (pintype "bidirectional"))
    )
    (net (code "8") (name "/BOOT_MODE") (class "Default")
      (node (ref "R24") (pin "1") (pinfunction "1_1") (pintype "passive"))
      (node (ref "R28") (pin "2") (pinfunction "2_2") (pintype "passive"))
      (node (ref "U3") (pin "18") (pinfunction "GPIO0_18") (pintype "bidirectional"))
    )
    (net (code "9") (name "/D+") (class "Default")
      (node (ref "R4") (pin "2") (pinfunction "2_2") (pintype "passive"))
      (node (ref "U5") (pin "4") (pinfunction "D+_4") (pintype "bidirectional"))
      (node (ref "U6") (pin "4") (pinfunction "D+_4") (pintype "bidirectional"))
    )
    (net (code "10") (name "/D-") (class "Default")
      (node (ref "R3") (pin "2") (pinfunction "2_2") (pintype "passive"))
      (node (ref "U5") (pin "3") (pinfunction "D-_3") (pintype "bidirectional"))
      (node (ref "U6") (pin "3") (pinfunction "D-_3") (pintype "bidirectional"))
    )
    (net (code "11") (name "/ESP_EN") (class "Default")
      (node (ref "R15") (pin "2") (pinfunction "2_2") (pintype "passive"))
      (node (ref "U3") (pin "3") (pinfunction "EN_3") (pintype "bidirectional"))
      (node (ref "U5") (pin "33") (pinfunction "PE2(~{HWB})_33") (pintype "bidirectional"))
      (node (ref "U6") (pin "33") (pinfunction "PE2(~{HWB})_33") (pintype "bidirectional"))
    )
    (net (code "12") (name "/GPIO2_LED") (class "Default")
      (node (ref "R29") (pin "2") (pinfunction "2_2") (pintype "passive"))
      (node (ref "R30") (pin "2") (pinfunction "2_2") (pintype "passive"))
      (node (ref "U3") (pin "17") (pinfunction "GPIO2_17") (pintype "bidirectional"))
    )
    (net (code "13") (name "/GPIO12") (class "Default")
      (node (ref "R16") (pin "2") (pinfunction "2_2") (pintype "passive"))
      (node (ref "U3") (pin "6") (pinfunction "GPIO12_6") (pintype "bidirectional"))
    )
    (net (code "14") (name "/GPIO13") (class "Default")
      (node (ref "R17") (pin "2") (pinfunction "2_2") (pintype "passive"))
      (node (ref "U3") (pin "7") (pinfunction "GPIO13_7") (pintype "bidirectional"))
    )
    (net (code "15") (name "/GPIO14") (class "Default")
      (node (ref "R18") (pin "2") (pinfunction "2_2") (pintype "passive"))
      (node (ref "U3") (pin "5") (pinfunction "GPIO14_5") (pintype "bidirectional"))
    )
    (net (code "16") (name "/GPIO15") (class "Default")
      (node (ref "R19") (pin "2") (pinfunction "2_2") (pintype "passive"))
      (node (ref "R21") (pin "2") (pinfunction "2_2") (pintype "passive"))
      (node (ref "U3") (pin "16") (pinfunction "GPIO15_16") (pintype "bidirectional"))
    )
    (net (code "17") (name "/GPIO16") (class "Default")
      (node (ref "R20") (pin "2") (pinfunction "2_2") (pintype "passive"))
      (node (ref "U3") (pin "4") (pinfunction "GPIO16_4") (pintype "bidirectional"))
    )
    (net (code "18") (name "/PIN_A0") (class "Default")
      (node (ref "J3") (pin "1") (pinfunction "1_1") (pintype "bidirectional"))
      (node (ref "U5") (pin "36") (pinfunction "PF7(ADC7/TDI)_36") (pintype "bidirectional"))
      (node (ref "U6") (pin "36") (pinfunction "PF7(ADC7/TDI)_36") (pintype "bidirectional"))
    )
    (net (code "19") (name "/PIN_A1") (class "Default")
      (node (ref "J3") (pin "2") (pinfunction "2_2") (pintype "bidirectional"))
      (node (ref "U5") (pin "37") (pinfunction "PF6(ADC6/TDO)_37") (pintype "bidirectional"))
      (node (ref "U6") (pin "37") (pinfunction "PF6(ADC6/TDO)_37") (pintype "bidirectional"))
    )
    (net (code "20") (name "/PIN_A2") (class "Default")
      (node (ref "J3") (pin "3") (pinfunction "3_3") (pintype "bidirectional"))
      (node (ref "U5") (pin "38") (pinfunction "PF5(ADC5/TMS)_38") (pintype "bidirectional"))
      (node (ref "U6") (pin "38") (pinfunction "PF5(ADC5/TMS)_38") (pintype "bidirectional"))
    )
    (net (code "21") (name "/PIN_A3") (class "Default")
      (node (ref "J3") (pin "4") (pinfunction "4_4") (pintype "bidirectional"))
      (node (ref "U5") (pin "39") (pinfunction "PF4(ADC4/TCK)_39") (pintype "bidirectional"))
      (node (ref "U6") (pin "39") (pinfunction "PF4(ADC4/TCK)_39") (pintype "bidirectional"))
    )
    (net (code "22") (name "/PIN_A4") (class "Default")
      (node (ref "J3") (pin "5") (pinfunction "5_5") (pintype "bidirectional"))
      (node (ref "U5") (pin "40") (pinfunction "PF1(ADC1)_40") (pintype "bidirectional"))
      (node (ref "U6") (pin "40") (pinfunction "PF1(ADC1)_40") (pintype "bidirectional"))
    )
    (net (code "23") (name "/PIN_A5") (class "Default")
      (node (ref "J3") (pin "6") (pinfunction "6_6") (pintype "bidirectional"))
      (node (ref "U5") (pin "41") (pinfunction "PF0(ADC0)_41") (pintype "bidirectional"))
      (node (ref "U6") (pin "41") (pinfunction "PF0(ADC0)_41") (pintype "bidirectional"))
    )
    (net (code "24") (name "/PIN_AREF") (class "Default")
      (node (ref "C21") (pin "1") (pinfunction "1_1") (pintype "passive"))
      (node (ref "J4") (pin "8") (pinfunction "8_8") (pintype "bidirectional"))
      (node (ref "U5") (pin "42") (pinfunction "AREF_42") (pintype "bidirectional"))
      (node (ref "U6") (pin "42") (pinfunction "AREF_42") (pintype "bidirectional"))
    )
    (net (code "25") (name "/PIN_D0") (class "Default")
      (node (ref "J5") (pin "1") (pinfunction "1_1") (pintype "bidirectional"))
      (node (ref "J8") (pin "1") (pinfunction "1_1") (pintype "bidirectional"))
      (node (ref "R22") (pin "2") (pinfunction "2_2") (pintype "passive"))
      (node (ref "TP12") (pin "TP") (pinfunction "TP_TP") (pintype "input"))
      (node (ref "U5") (pin "20") (pinfunction "PD2(RXD1/INT2)_20") (pintype "bidirectional"))
      (node (ref "U6") (pin "20") (pinfunction "PD2(RXD1/INT2)_20") (pintype "bidirectional"))
    )
    (net (code "26") (name "/PIN_D1") (class "Default")
      (node (ref "J5") (pin "2") (pinfunction "2_2") (pintype "bidirectional"))
      (node (ref "J8") (pin "2") (pinfunction "2_2") (pintype "bidirectional"))
      (node (ref "R23") (pin "2") (pinfunction "2_2") (pintype "passive"))
      (node (ref "TP13") (pin "TP") (pinfunction "TP_TP") (pintype "input"))
      (node (ref "U5") (pin "21") (pinfunction "PD3(TXD1/INT3)_21") (pintype "bidirectional"))
      (node (ref "U6") (pin "21") (pinfunction "PD3(TXD1/INT3)_21") (pintype "bidirectional"))
    )
    (net (code "27") (name "/PIN_D2_SDA") (class "Default")
      (node (ref "J5") (pin "3") (pinfunction "3_3") (pintype "bidirectional"))
      (node (ref "J6") (pin "2") (pinfunction "2_2") (pintype "bidirectional"))
      (node (ref "TP14") (pin "TP") (pinfunction "TP_TP") (pintype "input"))
      (node (ref "U3") (pin "19") (pinfunction "GPIO4_19") (pintype "bidirectional"))
      (node (ref "U4") (pin "5") (pinfunction "SDA_5") (pintype "bidirectional"))
      (node (ref "U5") (pin "19") (pinfunction "PD1(SDA/INT1)_19") (pintype "bidirectional"))
      (node (ref "U6") (pin "19") (pinfunction "PD1(SDA/INT1)_19") (pintype "bidirectional"))
    )
    (net (code "28") (name "/PIN_D3_SCL") (class "Default")
      (node (ref "J5") (pin "4") (pinfunction "4_4") (pintype "bidirectional"))
      (node (ref "J6") (pin "1") (pinfunction "1_1") (pintype "bidirectional"))
      (node (ref "TP15") (pin "TP") (pinfunction "TP_TP") (pintype "input"))
      (node (ref "U3") (pin "20") (pinfunction "GPIO5_20") (pintype "bidirectional"))
      (node (ref "U4") (pin "6") (pinfunction "SCL_6") (pintype "input"))
      (node (ref "U5") (pin "18") (pinfunction "PD0(OC0B/SCL/INT0)_18") (pintype "bidirectional"))
      (node (ref "U6") (pin "18") (pinfunction "PD0(OC0B/SCL/INT0)_18") (pintype "bidirectional"))
    )
    (net (code "29") (name "/PIN_D4") (class "Default")
      (node (ref "J5") (pin "5") (pinfunction "5_5") (pintype "bidirectional"))
      (node (ref "U5") (pin "25") (pinfunction "PD4(ICP1/ADC8)_25") (pintype "bidirectional"))
      (node (ref "U6") (pin "25") (pinfunction "PD4(ICP1/ADC8)_25") (pintype "bidirectional"))
    )
    (net (code "30") (name "/PIN_D5") (class "Default")
      (node (ref "J5") (pin "6") (pinfunction "6_6") (pintype "bidirectional"))
      (node (ref "U5") (pin "31") (pinfunction "PC6(OC3A/~{OC4A})_31") (pintype "bidirectional"))
      (node (ref "U6") (pin "31") (pinfunction "PC6(OC3A/~{OC4A})_31") (pintype "bidirectional"))
    )
    (net (code "31") (name "/PIN_D6") (class "Default")
      (node (ref "J5") (pin "7") (pinfunction "7_7") (pintype "bidirectional"))
      (node (ref "U5") (pin "27") (pinfunction "PD7(T0/OC4D/ADC10)_27") (pintype "bidirectional"))
      (node (ref "U6") (pin "27") (pinfunction "PD7(T0/OC4D/ADC10)_27") (pintype "bidirectional"))
    )
    (net (code "32") (name "/PIN_D7") (class "Default")
      (node (ref "J5") (pin "8") (pinfunction "8_8") (pintype "bidirectional"))
      (node (ref "U5") (pin "1") (pinfunction "PE6(INT.6/AIN0)_1") (pintype "bidirectional"))
      (node (ref "U6") (pin "1") (pinfunction "PE6(INT.6/AIN0)_1") (pintype "bidirectional"))
    )
    (net (code "33") (name "/PIN_D8") (class "Default")
      (node (ref "J4") (pin "1") (pinfunction "1_1") (pintype "bidirectional"))
      (node (ref "U5") (pin "28") (pinfunction "PB4(PCINT4/ADC11)_28") (pintype "bidirectional"))
      (node (ref "U6") (pin "28") (pinfunction "PB4(PCINT4/ADC11)_28") (pintype "bidirectional"))
    )
    (net (code "34") (name "/PIN_D9") (class "Default")
      (node (ref "J4") (pin "2") (pinfunction "2_2") (pintype "bidirectional"))
      (node (ref "U5") (pin "29") (pinfunction "PB5(PCINT5/OC1A/ADC12/~{OC4B})_29") (pintype "bidirectional"))
      (node (ref "U6") (pin "29") (pinfunction "PB5(PCINT5/OC1A/ADC12/~{OC4B})_29") (pintype "bidirectional"))
    )
    (net (code "35") (name "/PIN_D10") (class "Default")
      (node (ref "J4") (pin "3") (pinfunction "3_3") (pintype "bidirectional"))
      (node (ref "U5") (pin "30") (pinfunction "PB6(PCINT6/OC1B/OC4B/ADC13)_30") (pintype "bidirectional"))
      (node (ref "U6") (pin "30") (pinfunction "PB6(PCINT6/OC1B/OC4B/ADC13)_30") (pintype "bidirectional"))
    )
    (net (code "36") (name "/PIN_D11") (class "Default")
      (node (ref "J4") (pin "4") (pinfunction "4_4") (pintype "bidirectional"))
      (node (ref "U5") (pin "12") (pinfunction "PB7(PCINT7/OC0A/OC1C/~{RTS})_12") (pintype "bidirectional"))
      (node (ref "U6") (pin "12") (pinfunction "PB7(PCINT7/OC0A/OC1C/~{RTS})_12") (pintype "bidirectional"))
    )
    (net (code "37") (name "/PIN_D12") (class "Default")
      (node (ref "J4") (pin "5") (pinfunction "5_5") (pintype "bidirectional"))
      (node (ref "U5") (pin "26") (pinfunction "PD6(T1/ADC9/~{OC4D})_26") (pintype "bidirectional"))
      (node (ref "U6") (pin "26") (pinfunction "PD6(T1/ADC9/~{OC4D})_26") (pintype "bidirectional"))
    )
    (net (code "38") (name "/PIN_D13") (class "Default")
      (node (ref "J4") (pin "6") (pinfunction "6_6") (pintype "bidirectional"))
      (node (ref "R27") (pin "1") (pinfunction "1_1") (pintype "passive"))
      (node (ref "R28") (pin "1") (pinfunction "1_1") (pintype "passive"))
      (node (ref "U5") (pin "32") (pinfunction "PC7(ICP3/CLK0/OC4A)_32") (pintype "bidirectional"))
      (node (ref "U6") (pin "32") (pinfunction "PC7(ICP3/CLK0/OC4A)_32") (pintype "bidirectional"))
    )
    (net (code "39") (name "/RESET") (class "Default")
      (node (ref "C13") (pin "1") (pinfunction "1_1") (pintype "passive"))
      (node (ref "D3") (pin "+") (pinfunction "+_+") (pintype "passive"))
      (node (ref "J2") (pin "3") (pinfunction "3_3") (pintype "bidirectional"))
      (node (ref "J7") (pin "3") (pinfunction "3_3") (pintype "bidirectional"))
      (node (ref "R11") (pin "1") (pinfunction "1_1") (pintype "passive"))
      (node (ref "R12") (pin "1") (pinfunction "1_1") (pintype "passive"))
      (node (ref "R20") (pin "1") (pinfunction "1_1") (pintype "passive"))
      (node (ref "TP3") (pin "TP") (pinfunction "TP_TP") (pintype "input"))
      (node (ref "U5") (pin "13") (pinfunction "~{RESET}_13") (pintype "bidirectional"))
      (node (ref "U6") (pin "13") (pinfunction "~{RESET}_13") (pintype "bidirectional"))
    )
    (net (code "40") (name "/RST") (class "Default")
      (node (ref "R14") (pin "2") (pinfunction "2_2") (pintype "passive"))
      (node (ref "U3") (pin "1") (pinfunction "RST_1") (pintype "bidirectional"))
    )
    (net (code "41") (name "/RSTAT") (class "Default")
      (node (ref "C13") (pin "2") (pinfunction "2_2") (pintype "passive"))
      (node (ref "D2") (pin "-") (pinfunction "-_-") (pintype "passive"))
      (node (ref "R10") (pin "2") (pinfunction "2_2") (pintype "passive"))
      (node (ref "SW1") (pin "2") (pinfunction "2_2") (pintype "bidirectional"))
      (node (ref "TP11") (pin "TP") (pinfunction "TP_TP") (pintype "input"))
    )
    (net (code "42") (name "/RXD") (class "Default")
      (node (ref "R23") (pin "1") (pinfunction "1_1") (pintype "passive"))
      (node (ref "U3") (pin "21") (pinfunction "RXD_21") (pintype "bidirectional"))
    )
    (net (code "43") (name "/SW_F1") (class "Default")
      (node (ref "C10") (pin "2") (pinfunction "2_2") (pintype "passive"))
      (node (ref "C8") (pin "2") (pinfunction "2_2") (pintype "passive"))
      (node (ref "C9") (pin "2") (pinfunction "2_2") (pintype "passive"))
      (node (ref "L3") (pin "2") (pinfunction "2_2") (pintype "passive"))
      (node (ref "L4") (pin "1") (pinfunction "1_1") (pintype "passive"))
      (node (ref "R8") (pin "2") (pinfunction "2_2") (pintype "passive"))
    )
    (net (code "44") (name "/SW_VCC_OUT") (class "Default")
      (node (ref "C7") (pin "1") (pinfunction "1_1") (pintype "passive"))
      (node (ref "L3") (pin "1") (pinfunction "1_1") (pintype "passive"))
      (node (ref "U2") (pin "3") (pinfunction "SW_3") (pintype "bidirectional"))
    )
    (net (code "45") (name "/TXD") (class "Default")
      (node (ref "R22") (pin "1") (pinfunction "1_1") (pintype "passive"))
      (node (ref "U3") (pin "22") (pinfunction "TXD_22") (pintype "bidirectional"))
    )
    (net (code "46") (name "/UCAP") (class "Default")
      (node (ref "C22") (pin "2") (pinfunction "2_2") (pintype "passive"))
      (node (ref "U5") (pin "6") (pinfunction "UCAP_6") (pintype "bidirectional"))
      (node (ref "U6") (pin "6") (pinfunction "UCAP_6") (pintype "bidirectional"))
    )
    (net (code "47") (name "/UD+") (class "Default")
      (node (ref "ESD1") (pin "2") (pinfunction "IO1_2") (pintype "bidirectional"))
      (node (ref "R4") (pin "1") (pinfunction "1_1") (pintype "passive"))
      (node (ref "TP7") (pin "TP") (pinfunction "TP_TP") (pintype "input"))
      (node (ref "USB1") (pin "3") (pinfunction "DP_3") (pintype "bidirectional"))
    )
    (net (code "48") (name "/UD-") (class "Default")
      (node (ref "ESD1") (pin "3") (pinfunction "IO2_3") (pintype "bidirectional"))
      (node (ref "R3") (pin "1") (pinfunction "1_1") (pintype "passive"))
      (node (ref "TP6") (pin "TP") (pinfunction "TP_TP") (pintype "input"))
      (node (ref "USB1") (pin "2") (pinfunction "DM_2") (pintype "bidirectional"))
    )
    (net (code "49") (name "/UGND") (class "Default")
      (node (ref "C22") (pin "1") (pinfunction "1_1") (pintype "passive"))
      (node (ref "ESD1") (pin "1") (pinfunction "GND_1") (pintype "bidirectional"))
      (node (ref "L2") (pin "2") (pinfunction "2_2") (pintype "passive"))
      (node (ref "TP8") (pin "TP") (pinfunction "TP_TP") (pintype "input"))
      (node (ref "U5") (pin "5") (pinfunction "UGND_5") (pintype "bidirectional"))
      (node (ref "U6") (pin "5") (pinfunction "UGND_5") (pintype "bidirectional"))
      (node (ref "USB1") (pin "5") (pinfunction "GND_5") (pintype "bidirectional"))
    )
    (net (code "50") (name "/UVCC") (class "Default")
      (node (ref "ESD1") (pin "4") (pinfunction "VCC_4") (pintype "bidirectional"))
      (node (ref "F1") (pin "1") (pinfunction "1_1") (pintype "bidirectional"))
      (node (ref "TP5") (pin "TP") (pinfunction "TP_TP") (pintype "input"))
      (node (ref "USB1") (pin "1") (pinfunction "VCC_1") (pintype "bidirectional"))
    )
    (net (code "51") (name "/VIN") (class "Default")
      (node (ref "D1") (pin "-") (pinfunction "-_-") (pintype "passive"))
      (node (ref "J1") (pin "VCC1") (pinfunction "+_VCC1") (pintype "bidirectional"))
      (node (ref "J1") (pin "VCC2") (pinfunction "+_VCC2") (pintype "bidirectional"))
      (node (ref "J1") (pin "VCC3") (pinfunction "+_VCC3") (pintype "bidirectional"))
      (node (ref "J1") (pin "VCC4") (pinfunction "+_VCC4") (pintype "bidirectional"))
      (node (ref "J2") (pin "8") (pinfunction "8_8") (pintype "bidirectional"))
      (node (ref "Q1") (pin "3") (pinfunction "D_3") (pintype "passive"))
      (node (ref "TP9") (pin "TP") (pinfunction "TP_TP") (pintype "input"))
    )
    (net (code "52") (name "/VUSB") (class "Default")
      (node (ref "F1") (pin "2") (pinfunction "2_2") (pintype "bidirectional"))
      (node (ref "Q2") (pin "3") (pinfunction "D_3") (pintype "passive"))
      (node (ref "U5") (pin "2") (pinfunction "UVCC_2") (pintype "bidirectional"))
      (node (ref "U5") (pin "7") (pinfunction "VBUS_7") (pintype "bidirectional"))
      (node (ref "U6") (pin "2") (pinfunction "UVCC_2") (pintype "bidirectional"))
      (node (ref "U6") (pin "7") (pinfunction "VBUS_7") (pintype "bidirectional"))
    )
    (net (code "53") (name "/XTAL1") (class "Default")
      (node (ref "C14") (pin "2") (pinfunction "2_2") (pintype "passive"))
      (node (ref "R13") (pin "2") (pinfunction "2_2") (pintype "passive"))
      (node (ref "U5") (pin "17") (pinfunction "XTAL1_17") (pintype "bidirectional"))
      (node (ref "U6") (pin "17") (pinfunction "XTAL1_17") (pintype "bidirectional"))
      (node (ref "X1") (pin "P$1") (pinfunction "P$1_P$1") (pintype "passive"))
    )
    (net (code "54") (name "/XTAL2") (class "Default")
      (node (ref "C15") (pin "2") (pinfunction "2_2") (pintype "passive"))
      (node (ref "R13") (pin "1") (pinfunction "1_1") (pintype "passive"))
      (node (ref "U5") (pin "16") (pinfunction "XTAL2_16") (pintype "bidirectional"))
      (node (ref "U6") (pin "16") (pinfunction "XTAL2_16") (pintype "bidirectional"))
      (node (ref "X1") (pin "P$3") (pinfunction "P$2_P$3") (pintype "passive"))
    )
    (net (code "55") (name "GND") (class "Default")
      (node (ref "C1") (pin "1") (pinfunction "1_1") (pintype "passive"))
      (node (ref "C10") (pin "1") (pinfunction "1_1") (pintype "passive"))
      (node (ref "C11") (pin "1") (pinfunction "1_1") (pintype "passive"))
      (node (ref "C12") (pin "1") (pinfunction "1_1") (pintype "passive"))
      (node (ref "C14") (pin "1") (pinfunction "1_1") (pintype "passive"))
      (node (ref "C15") (pin "1") (pinfunction "1_1") (pintype "passive"))
      (node (ref "C16") (pin "2") (pinfunction "2_2") (pintype "passive"))
      (node (ref "C17") (pin "2") (pinfunction "2_2") (pintype "passive"))
      (node (ref "C18") (pin "2") (pinfunction "2_2") (pintype "passive"))
      (node (ref "C19") (pin "2") (pinfunction "2_2") (pintype "passive"))
      (node (ref "C2") (pin "1") (pinfunction "1_1") (pintype "passive"))
      (node (ref "C20") (pin "2") (pinfunction "2_2") (pintype "passive"))
      (node (ref "C21") (pin "2") (pinfunction "2_2") (pintype "passive"))
      (node (ref "C23") (pin "2") (pinfunction "2_2") (pintype "passive"))
      (node (ref "C3") (pin "1") (pinfunction "1_1") (pintype "passive"))
      (node (ref "C4") (pin "1") (pinfunction "1_1") (pintype "passive"))
      (node (ref "C5") (pin "1") (pinfunction "1_1") (pintype "passive"))
      (node (ref "C6") (pin "1") (pinfunction "1_1") (pintype "passive"))
      (node (ref "C8") (pin "1") (pinfunction "1_1") (pintype "passive"))
      (node (ref "C9") (pin "1") (pinfunction "1_1") (pintype "passive"))
      (node (ref "D1") (pin "+") (pinfunction "+_+") (pintype "passive"))
      (node (ref "D5") (pin "-") (pinfunction "-_-") (pintype "passive"))
      (node (ref "D6") (pin "-") (pinfunction "-_-") (pintype "passive"))
      (node (ref "D7") (pin "-") (pinfunction "-_-") (pintype "passive"))
      (node (ref "J1") (pin "CDN1") (pinfunction "CDN_CDN1") (pintype "bidirectional"))
      (node (ref "J1") (pin "CDN2") (pinfunction "CDN_CDN2") (pintype "bidirectional"))
      (node (ref "J1") (pin "CDN3") (pinfunction "CDN_CDN3") (pintype "bidirectional"))
      (node (ref "J1") (pin "CDN4") (pinfunction "CDN_CDN4") (pintype "bidirectional"))
      (node (ref "J1") (pin "GND1") (pinfunction "-_GND1") (pintype "bidirectional"))
      (node (ref "J1") (pin "GND2") (pinfunction "-_GND2") (pintype "bidirectional"))
      (node (ref "J1") (pin "GND3") (pinfunction "-_GND3") (pintype "bidirectional"))
      (node (ref "J1") (pin "GND4") (pinfunction "-_GND4") (pintype "bidirectional"))
      (node (ref "J2") (pin "6") (pinfunction "6_6") (pintype "bidirectional"))
      (node (ref "J2") (pin "7") (pinfunction "7_7") (pintype "bidirectional"))
      (node (ref "J4") (pin "7") (pinfunction "7_7") (pintype "bidirectional"))
      (node (ref "J6") (pin "4") (pinfunction "4_4") (pintype "bidirectional"))
      (node (ref "J7") (pin "4") (pinfunction "4_4") (pintype "bidirectional"))
      (node (ref "J8") (pin "4") (pinfunction "4_4") (pintype "bidirectional"))
      (node (ref "L2") (pin "1") (pinfunction "1_1") (pintype "passive"))
      (node (ref "Q1") (pin "1") (pinfunction "G_1") (pintype "passive"))
      (node (ref "R2") (pin "1") (pinfunction "1_1") (pintype "passive"))
      (node (ref "R21") (pin "1") (pinfunction "1_1") (pintype "passive"))
      (node (ref "R7") (pin "1") (pinfunction "1_1") (pintype "passive"))
      (node (ref "SW1") (pin "1") (pinfunction "1_1") (pintype "bidirectional"))
      (node (ref "TP10") (pin "TP") (pinfunction "TP_TP") (pintype "input"))
      (node (ref "TP18") (pin "TP") (pinfunction "TP_TP") (pintype "input"))
      (node (ref "TP19") (pin "TP") (pinfunction "TP_TP") (pintype "input"))
      (node (ref "U1") (pin "1") (pinfunction "GND_1") (pintype "bidirectional"))
      (node (ref "U2") (pin "4") (pinfunction "GND_4") (pintype "bidirectional"))
      (node (ref "U3") (pin "15") (pinfunction "GND_15") (pintype "bidirectional"))
      (node (ref "U4") (pin "4") (pinfunction "GND_4") (pintype "power_in"))
      (node (ref "U5") (pin "15") (pinfunction "GND_15") (pintype "bidirectional"))
      (node (ref "U5") (pin "23") (pinfunction "GND_23") (pintype "bidirectional"))
      (node (ref "U5") (pin "35") (pinfunction "GND_35") (pintype "bidirectional"))
      (node (ref "U5") (pin "43") (pinfunction "GND_43") (pintype "bidirectional"))
      (node (ref "U5") (pin "TAB") (pinfunction "GND_TAB") (pintype "bidirectional"))
      (node (ref "U6") (pin "15") (pinfunction "GND_15") (pintype "bidirectional"))
      (node (ref "U6") (pin "23") (pinfunction "GND_23") (pintype "bidirectional"))
      (node (ref "U6") (pin "35") (pinfunction "GND_35") (pintype "bidirectional"))
      (node (ref "U6") (pin "43") (pinfunction "GND_43") (pintype "bidirectional"))
      (node (ref "USB1") (pin "S1") (pinfunction "GND_S1") (pintype "bidirectional"))
      (node (ref "USB1") (pin "S2_1") (pinfunction "GND_S2_1") (pintype "bidirectional"))
      (node (ref "USB1") (pin "S2_2") (pinfunction "GND_S2_2") (pintype "bidirectional"))
      (node (ref "USB1") (pin "S2_3") (pinfunction "GND_S2_3") (pintype "bidirectional"))
      (node (ref "USB1") (pin "S3") (pinfunction "GND_S3") (pintype "bidirectional"))
      (node (ref "USB1") (pin "S4") (pinfunction "GND_S4") (pintype "bidirectional"))
      (node (ref "USB1") (pin "S5_1") (pinfunction "GND_S5_1") (pintype "bidirectional"))
      (node (ref "USB1") (pin "S5_2") (pinfunction "GND_S5_2") (pintype "bidirectional"))
      (node (ref "USB1") (pin "S5_3") (pinfunction "GND_S5_3") (pintype "bidirectional"))
      (node (ref "USB1") (pin "S6") (pinfunction "GND_S6") (pintype "bidirectional"))
      (node (ref "X1") (pin "P$2") (pinfunction "GND1_P$2") (pintype "power_in"))
      (node (ref "X1") (pin "P$4") (pinfunction "GND2_P$4") (pintype "power_in"))
    )
    (net (code "56") (name "Net-(C7-Pad2)") (class "Default")
      (node (ref "C7") (pin "2") (pinfunction "2_2") (pintype "passive"))
      (node (ref "R5") (pin "2") (pinfunction "2_2") (pintype "passive"))
    )
    (net (code "57") (name "Net-(C16-Pad1)") (class "Default")
      (node (ref "C16") (pin "1") (pinfunction "1_1") (pintype "passive"))
      (node (ref "R12") (pin "2") (pinfunction "2_2") (pintype "passive"))
    )
    (net (code "58") (name "Net-(D4-Pad-)") (class "Default")
      (node (ref "D4") (pin "-") (pinfunction "-_-") (pintype "passive"))
      (node (ref "R30") (pin "1") (pinfunction "1_1") (pintype "passive"))
    )
    (net (code "59") (name "Net-(D5-Pad+)") (class "Default")
      (node (ref "D5") (pin "+") (pinfunction "+_+") (pintype "passive"))
      (node (ref "R25") (pin "2") (pinfunction "2_2") (pintype "passive"))
    )
    (net (code "60") (name "Net-(D6-Pad+)") (class "Default")
      (node (ref "D6") (pin "+") (pinfunction "+_+") (pintype "passive"))
      (node (ref "R26") (pin "2") (pinfunction "2_2") (pintype "passive"))
    )
    (net (code "61") (name "Net-(D7-Pad+)") (class "Default")
      (node (ref "D7") (pin "+") (pinfunction "+_+") (pintype "passive"))
      (node (ref "R27") (pin "2") (pinfunction "2_2") (pintype "passive"))
    )
    (net (code "62") (name "Net-(Q1-S)") (class "Default")
      (node (ref "L1") (pin "1") (pinfunction "1_1") (pintype "passive"))
      (node (ref "Q1") (pin "2") (pinfunction "S_2") (pintype "passive"))
    )
    (net (code "63") (name "Net-(Q2-G)") (class "Default")
      (node (ref "Q2") (pin "1") (pinfunction "G_1") (pintype "passive"))
      (node (ref "R9") (pin "2") (pinfunction "2_2") (pintype "passive"))
    )
    (net (code "64") (name "Net-(R6-Pad2)") (class "Default")
      (node (ref "R6") (pin "2") (pinfunction "2_2") (pintype "passive"))
      (node (ref "R7") (pin "2") (pinfunction "2_2") (pintype "passive"))
      (node (ref "R8") (pin "1") (pinfunction "1_1") (pintype "passive"))
    )
    (net (code "65") (name "Net-(U2-BS)") (class "Default")
      (node (ref "R5") (pin "1") (pinfunction "1_1") (pintype "passive"))
      (node (ref "U2") (pin "5") (pinfunction "BS_5") (pintype "bidirectional"))
    )
    (net (code "66") (name "Net-(U2-EN{slash}SYNC)") (class "Default")
      (node (ref "R1") (pin "2") (pinfunction "2_2") (pintype "passive"))
      (node (ref "R2") (pin "2") (pinfunction "2_2") (pintype "passive"))
      (node (ref "U2") (pin "6") (pinfunction "EN/SYNC_6") (pintype "bidirectional"))
    )
    (net (code "67") (name "Net-(U2-FB)") (class "Default")
      (node (ref "R6") (pin "1") (pinfunction "1_1") (pintype "passive"))
      (node (ref "U2") (pin "8") (pinfunction "FB_8") (pintype "bidirectional"))
    )
    (net (code "68") (name "Net-(U2-IN)") (class "Default")
      (node (ref "C2") (pin "2") (pinfunction "2_2") (pintype "passive"))
      (node (ref "C4") (pin "2") (pinfunction "2_2") (pintype "passive"))
      (node (ref "L1") (pin "2") (pinfunction "2_2") (pintype "passive"))
      (node (ref "R1") (pin "1") (pinfunction "1_1") (pintype "passive"))
      (node (ref "U2") (pin "2") (pinfunction "IN_2") (pintype "bidirectional"))
    )
    (net (code "69") (name "Net-(U2-SS)") (class "Default")
      (node (ref "C6") (pin "2") (pinfunction "2_2") (pintype "passive"))
      (node (ref "U2") (pin "1") (pinfunction "SS_1") (pintype "bidirectional"))
    )
    (net (code "70") (name "Net-(U2-VCC)") (class "Default")
      (node (ref "C5") (pin "2") (pinfunction "2_2") (pintype "passive"))
      (node (ref "U2") (pin "7") (pinfunction "VCC_7") (pintype "bidirectional"))
    )
    (net (code "71") (name "unconnected-(J2-Pad1)") (class "Default")
      (node (ref "J2") (pin "1") (pinfunction "1_1") (pintype "bidirectional"))
    )
    (net (code "72") (name "unconnected-(U3-ADC-Pad2)") (class "Default")
      (node (ref "U3") (pin "2") (pinfunction "ADC_2") (pintype "bidirectional"))
    )
    (net (code "73") (name "unconnected-(U3-CS0-Pad9)") (class "Default")
      (node (ref "U3") (pin "9") (pinfunction "CS0_9") (pintype "bidirectional"))
    )
    (net (code "74") (name "unconnected-(U3-IO9-Pad11)") (class "Default")
      (node (ref "U3") (pin "11") (pinfunction "IO9_11") (pintype "bidirectional"))
    )
    (net (code "75") (name "unconnected-(U3-IO10-Pad12)") (class "Default")
      (node (ref "U3") (pin "12") (pinfunction "IO10_12") (pintype "bidirectional"))
    )
    (net (code "76") (name "unconnected-(U3-MISO-Pad10)") (class "Default")
      (node (ref "U3") (pin "10") (pinfunction "MISO_10") (pintype "bidirectional"))
    )
    (net (code "77") (name "unconnected-(U3-MOSI-Pad13)") (class "Default")
      (node (ref "U3") (pin "13") (pinfunction "MOSI_13") (pintype "bidirectional"))
    )
    (net (code "78") (name "unconnected-(U3-SCLK-Pad14)") (class "Default")
      (node (ref "U3") (pin "14") (pinfunction "SCLK_14") (pintype "bidirectional"))
    )
    (net (code "79") (name "unconnected-(U4-NC1-Pad1)") (class "Default")
      (node (ref "U4") (pin "1") (pinfunction "NC1_1") (pintype "no_connect"))
    )
    (net (code "80") (name "unconnected-(U4-NC2-Pad2)") (class "Default")
      (node (ref "U4") (pin "2") (pinfunction "NC2_2") (pintype "no_connect"))
    )
    (net (code "81") (name "unconnected-(U4-NC3-Pad3)") (class "Default")
      (node (ref "U4") (pin "3") (pinfunction "NC3_3") (pintype "no_connect"))
    )
    (net (code "82") (name "unconnected-(U4-NC4-Pad7)") (class "Default")
      (node (ref "U4") (pin "7") (pinfunction "NC4_7") (pintype "no_connect"))
    )
    (net (code "83") (name "unconnected-(USB1-ID-Pad4)") (class "Default")
      (node (ref "USB1") (pin "4") (pinfunction "ID_4") (pintype "bidirectional"))
    )
  )
)
